# Power_management.net
KiCad netlist of a schematic drawn in Altium Designer
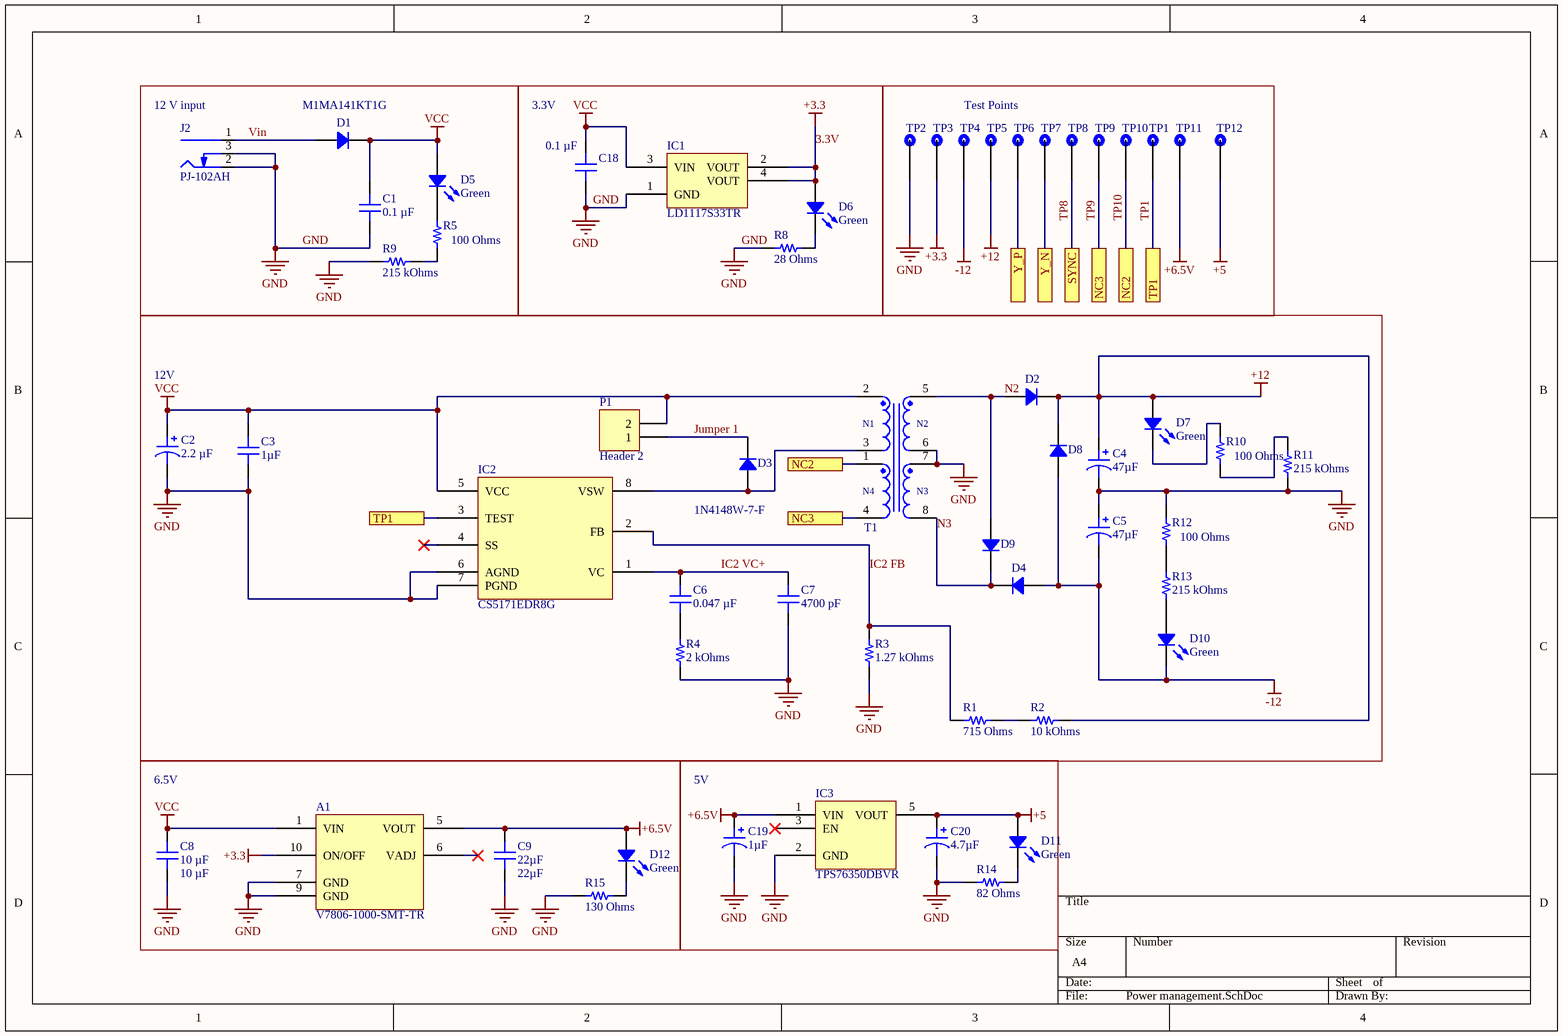
[diagram p0: Power management.SchDoc]

(export (version "E")
  (design (tool "Eeschema 10.0.6"))
  (components
    (comp (ref "A1")
      (value "V7806-1000-SMT-TR")
      (footprint "CUI V78")
      (description "DC DC CONVERTER 6.5V 7W")
      (libsource (lib "Celestial Altium Library - altium_library(1)") (part "CUI V78"))
    )
    (comp (ref "C1")
      (value "0.1 µF")
      (footprint "CAP 0805_2012")
      (description ".100UF 50.0V")
      (fields (field (name "PART NUMBER") "C0805X104K5RAC7210") (field (name "MANUFACTURER") "KEMET"))
      (libsource (lib "Celestial Altium Library - altium_library(1)") (part "Capacitor"))
    )
    (comp (ref "C2")
      (value "2.2 µF")
      (footprint "CAP AL TH D8 L3.5 H12.5")
      (description "CAP ALUM 2.2UF 20% 400V RADIAL")
      (fields (field (name "PART NUMBER") "UVY2G2R2MPD") (field (name "MANUFACTURER") "Nichicon"))
      (libsource (lib "Celestial Altium Library - altium_library(1)") (part "Polarised Capacitor"))
    )
    (comp (ref "C3")
      (value "1µF")
      (footprint "CAP 1206_3216 - 1.0MM")
      (description "CAP CER 1UF 50V X7R 1206")
      (fields (field (name "PART NUMBER") "12065C105K4Z2A") (field (name "MANUFACTURER") "AVX Corporation"))
      (libsource (lib "Celestial Altium Library - altium_library(1)") (part "Capacitor"))
    )
    (comp (ref "C4")
      (value "47µF")
      (footprint "CAP TH ALUM ELEC D6.30mm S2.50mm H12.70mm")
      (description "AL LYTIC, RADIAL, 50VDC, 47UF")
      (fields
        (field (name "PART NUMBER") "EEU-FR1H470")
        (field (name "MANUFACTURER") "Panasonic Electronic Components")
      )
      (libsource (lib "Celestial Altium Library - altium_library(1)") (part "Polarised Capacitor"))
    )
    (comp (ref "C5")
      (value "47µF")
      (footprint "CAP TH ALUM ELEC D6.30mm S2.50mm H12.70mm")
      (description "AL LYTIC, RADIAL, 50VDC, 47UF")
      (fields
        (field (name "PART NUMBER") "EEU-FR1H470")
        (field (name "MANUFACTURER") "Panasonic Electronic Components")
      )
      (libsource (lib "Celestial Altium Library - altium_library(1)") (part "Polarised Capacitor"))
    )
    (comp (ref "C6")
      (value "0.047 µF")
      (footprint "CAP 1206_3216 - 0.8MM")
      (description "CAP CER 1206 47NF 50V X7R 10%")
      (fields (field (name "PART NUMBER") "C1206C473K5RECAUTO") (field (name "MANUFACTURER") "KEMET"))
      (libsource (lib "Celestial Altium Library - altium_library(1)") (part "Capacitor"))
    )
    (comp (ref "C7")
      (value "4700 pF")
      (footprint "CAP 1206_3216 - 0.8MM")
      (description "CAP1206 COG 4700PF 2% 50V")
      (fields
        (field (name "PART NUMBER") "GMC31CG472G50NT")
        (field (name "MANUFACTURER") "Cal-Chip Electronics, Inc.")
      )
      (libsource (lib "Celestial Altium Library - altium_library(1)") (part "Capacitor"))
    )
    (comp (ref "C8")
      (value "10 µF")
      (footprint "CAP 1210_3225 - 1MM")
      (description "CAP CER 10UF 50V X7S 1210")
      (fields (field (name "PART NUMBER") "GCJ32EC71H106KA01L") (field (name "ALTIUM_VALUE") "10 µF"))
      (libsource (lib "Celestial Altium Library - altium_library(1)") (part "Capacitor"))
    )
    (comp (ref "C9")
      (value "22µF")
      (footprint "CAP 1210_3225 - 2.8MM")
      (description "CAP CER 22UF 25V X5R 1210")
      (fields (field (name "PART NUMBER") "12103D226KAT2A") (field (name "ALTIUM_VALUE") "22µF"))
      (libsource (lib "Celestial Altium Library - altium_library(1)") (part "Capacitor"))
    )
    (comp (ref "C18")
      (value "0.1 µF")
      (footprint "CAP 1210_3225 - 1MM")
      (description ".100UF  200V")
      (fields (field (name "PART NUMBER") "C1210J104K2RAC7800") (field (name "MANUFACTURER") "KEMET"))
      (libsource (lib "Celestial Altium Library - altium_library(1)") (part "Capacitor"))
    )
    (comp (ref "C19")
      (value "1µF")
      (footprint "CAP TH ALUM ELEC D4.00mm S1.50mm H6.00mm")
      (description "CAP ALUM 1UF 20% 35V RADIAL")
      (fields (field (name "PART NUMBER") "UMF1V010MDD") (field (name "MANUFACTURER") "Nichicon"))
      (libsource (lib "Celestial Altium Library - altium_library(1)") (part "Polarised Capacitor"))
    )
    (comp (ref "C20")
      (value "4.7µF")
      (footprint "CAP TH ALUM ELEC D4.00mm S1.50mm H6.00mm")
      (description "CAP ALUM 4.7UF 20% 35V RADIAL")
      (fields (field (name "PART NUMBER") "UMF1V4R7MDD") (field (name "MANUFACTURER") "Nichicon"))
      (libsource (lib "Celestial Altium Library - altium_library(1)") (part "Polarised Capacitor"))
    )
    (comp (ref "D1")
      (value "M1MA141KT1G")
      (footprint "DIODES SOT-323-3")
      (description "DIODE GEN PURP 40V 100MA SC70-3")
      (fields (field (name "MANUFACTURER") "ON Semiconductor"))
      (libsource (lib "Celestial Altium Library - altium_library(1)") (part "Diode"))
    )
    (comp (ref "D2")
      (value "MBRS140T3G")
      (footprint "DO214AA SMB")
      (description "DIODE SCHOTTKY 40V 1A SMB")
      (fields (field (name "MANUFACTURER") "ON Semiconductor"))
      (libsource (lib "Celestial Altium Library - altium_library(1)") (part "Diode"))
    )
    (comp (ref "D3")
      (value "1N4148W-7-F")
      (footprint "SOD-123")
      (description "DIODE GEN PURP 100V 300MA SOD123")
      (fields (field (name "MANUFACTURER") "Diodes Incorporated"))
      (libsource (lib "Celestial Altium Library - altium_library(1)") (part "Diode"))
    )
    (comp (ref "D4")
      (value "MBRS140T3G")
      (footprint "DO214AA SMB")
      (description "DIODE SCHOTTKY 40V 1A SMB")
      (fields (field (name "MANUFACTURER") "ON Semiconductor"))
      (libsource (lib "Celestial Altium Library - altium_library(1)") (part "Diode"))
    )
    (comp (ref "D5")
      (value "Green")
      (footprint "LED 1206_3216 GREEN")
      (description "LED GREEN CLEAR 2SMD")
      (fields (field (name "PART NUMBER") "XZVG60W") (field (name "MANUFACTURER") "SunLED"))
      (libsource (lib "Celestial Altium Library - altium_library(1)") (part "LED"))
    )
    (comp (ref "D6")
      (value "Green")
      (footprint "LED 1206_3216 GREEN")
      (description "LED GREEN CLEAR 2SMD")
      (fields (field (name "PART NUMBER") "XZVG60W") (field (name "MANUFACTURER") "SunLED"))
      (libsource (lib "Celestial Altium Library - altium_library(1)") (part "LED"))
    )
    (comp (ref "D7")
      (value "Green")
      (footprint "LED 1206_3216 GREEN")
      (description "LED GREEN CLEAR 2SMD")
      (fields (field (name "PART NUMBER") "XZVG60W") (field (name "MANUFACTURER") "SunLED"))
      (libsource (lib "Celestial Altium Library - altium_library(1)") (part "LED"))
    )
    (comp (ref "D8")
      (value "MBRS140T3G")
      (footprint "DO214AA SMB")
      (description "DIODE SCHOTTKY 40V 1A SMB")
      (fields (field (name "MANUFACTURER") "ON Semiconductor"))
      (libsource (lib "Celestial Altium Library - altium_library(1)") (part "Diode"))
    )
    (comp (ref "D9")
      (value "MBRS140T3G")
      (footprint "DO214AA SMB")
      (description "DIODE SCHOTTKY 40V 1A SMB")
      (fields (field (name "MANUFACTURER") "ON Semiconductor"))
      (libsource (lib "Celestial Altium Library - altium_library(1)") (part "Diode"))
    )
    (comp (ref "D10")
      (value "Green")
      (footprint "LED 1206_3216 GREEN")
      (description "LED GREEN CLEAR 2SMD")
      (fields (field (name "PART NUMBER") "XZVG60W") (field (name "MANUFACTURER") "SunLED"))
      (libsource (lib "Celestial Altium Library - altium_library(1)") (part "LED"))
    )
    (comp (ref "D11")
      (value "Green")
      (footprint "LED 1206_3216 GREEN")
      (description "LED GREEN CLEAR 2SMD")
      (fields (field (name "PART NUMBER") "XZVG60W") (field (name "MANUFACTURER") "SunLED"))
      (libsource (lib "Celestial Altium Library - altium_library(1)") (part "LED"))
    )
    (comp (ref "D12")
      (value "Green")
      (footprint "LED 1206_3216 GREEN")
      (description "LED GREEN CLEAR 2SMD")
      (fields (field (name "PART NUMBER") "XZVG60W") (field (name "MANUFACTURER") "SunLED"))
      (libsource (lib "Celestial Altium Library - altium_library(1)") (part "LED"))
    )
    (comp (ref "IC1")
      (value "LD1117S33TR")
      (footprint "ST SOT-223")
      (description "IC REG LINEAR 3.3V 800MA SOT223")
      (fields (field (name "MANUFACTURER") "STMicroelectronics"))
      (libsource (lib "Celestial Altium Library - altium_library(1)") (part "ST LD1117"))
    )
    (comp (ref "IC2")
      (value "CS5171EDR8G")
      (footprint "ON SEMI SO-8")
      (description "IC REG MULT CONFG ADJ 1.5A 8SOIC")
      (fields (field (name "MANUFACTURER") "ON Semiconductor"))
      (libsource (lib "Celestial Altium Library - altium_library(1)") (part "ON Semi CS5171/3"))
    )
    (comp (ref "IC3")
      (value "TPS76350DBVR")
      (footprint "TI SOT-23-5 DBV")
      (description "IC REG LINEAR 5V 150MA SOT23-5")
      (fields (field (name "MANUFACTURER") "Texas Instruments"))
      (libsource (lib "Celestial Altium Library - altium_library(1)") (part "TI TPS763xx"))
    )
    (comp (ref "J2")
      (value "PJ-102AH")
      (footprint "CUI PJ-102AH")
      (description "CONN PWR JACK 2X5.5MM SOLDER")
      (fields (field (name "MANUFACTURER") "CUI Devices"))
      (libsource (lib "Celestial Altium Library - altium_library(1)") (part "Barrel Connector"))
    )
    (comp (ref "P1")
      (value "Header 2")
      (footprint "HDR1X2")
      (description "Header, 2-Pin")
      (fields (field (name "PUBLISHER") "Altium Limited"))
      (libsource (lib "Miscellaneous Connectors") (part "Header 2"))
    )
    (comp (ref "R1")
      (value "715 Ohms")
      (footprint "RES 1210_3225")
      (description "RES SMD 715 OHM 1% 1/2W 1210")
      (fields (field (name "PART NUMBER") "CRCW1210715RFKEA") (field (name "MANUFACTURER") "Vishay Dale"))
      (libsource (lib "Celestial Altium Library - altium_library(1)") (part "Resistor"))
    )
    (comp (ref "R2")
      (value "10 kOhms")
      (footprint "RES 1210_3225")
      (description "RES SMD 10K OHM 0.5% 1/2W 1210")
      (fields
        (field (name "PART NUMBER") "ERJ-P14D1002U")
        (field (name "MANUFACTURER") "Panasonic Electronic Components")
      )
      (libsource (lib "Celestial Altium Library - altium_library(1)") (part "Resistor"))
    )
    (comp (ref "R3")
      (value "1.27 kOhms")
      (footprint "RES 1210_3225")
      (description "RES SMD 1.27K OHM 1% 1/2W 1210")
      (fields
        (field (name "PART NUMBER") "ERJ-14NF1271U")
        (field (name "MANUFACTURER") "Panasonic Electronic Components")
      )
      (libsource (lib "Celestial Altium Library - altium_library(1)") (part "Resistor"))
    )
    (comp (ref "R4")
      (value "2 kOhms")
      (footprint "RES 1210_3225")
      (description "RES 2K OHM 5% 1/2W 1210")
      (fields (field (name "PART NUMBER") "RC1210JR-072KL") (field (name "MANUFACTURER") "Yageo"))
      (libsource (lib "Celestial Altium Library - altium_library(1)") (part "Resistor"))
    )
    (comp (ref "R5")
      (value "100 Ohms")
      (footprint "RES 2512_6432")
      (description "RES 100 OHM 1% 1W 2512")
      (fields
        (field (name "PART NUMBER") "RK73H3ATTE1000F")
        (field (name "MANUFACTURER") "KOA Speer Electronics, Inc.")
      )
      (libsource (lib "Celestial Altium Library - altium_library(1)") (part "Resistor"))
    )
    (comp (ref "R8")
      (value "28 Ohms")
      (footprint "RES 2512_6432")
      (description "RES 28 OHM 1% 1W 2512")
      (fields
        (field (name "PART NUMBER") "RK73H3ATTE28R0F")
        (field (name "MANUFACTURER") "KOA Speer Electronics, Inc.")
      )
      (libsource (lib "Celestial Altium Library - altium_library(1)") (part "Resistor"))
    )
    (comp (ref "R9")
      (value "215 kOhms")
      (footprint "RES 2512_6432")
      (description "RES SMD 215K OHM 1% 1W 2512")
      (fields (field (name "PART NUMBER") "CRCW2512215KFKEG") (field (name "MANUFACTURER") "Vishay Dale"))
      (libsource (lib "Celestial Altium Library - altium_library(1)") (part "Resistor"))
    )
    (comp (ref "R10")
      (value "100 Ohms")
      (footprint "RES 2512_6432")
      (description "RES 100 OHM 1% 1W 2512")
      (fields
        (field (name "PART NUMBER") "RK73H3ATTE1000F")
        (field (name "MANUFACTURER") "KOA Speer Electronics, Inc.")
      )
      (libsource (lib "Celestial Altium Library - altium_library(1)") (part "Resistor"))
    )
    (comp (ref "R11")
      (value "215 kOhms")
      (footprint "RES 2512_6432")
      (description "RES SMD 215K OHM 1% 1W 2512")
      (fields (field (name "PART NUMBER") "CRCW2512215KFKEG") (field (name "MANUFACTURER") "Vishay Dale"))
      (libsource (lib "Celestial Altium Library - altium_library(1)") (part "Resistor"))
    )
    (comp (ref "R12")
      (value "100 Ohms")
      (footprint "RES 2512_6432")
      (description "RES 100 OHM 1% 1W 2512")
      (fields
        (field (name "PART NUMBER") "RK73H3ATTE1000F")
        (field (name "MANUFACTURER") "KOA Speer Electronics, Inc.")
      )
      (libsource (lib "Celestial Altium Library - altium_library(1)") (part "Resistor"))
    )
    (comp (ref "R13")
      (value "215 kOhms")
      (footprint "RES 2512_6432")
      (description "RES SMD 215K OHM 1% 1W 2512")
      (fields (field (name "PART NUMBER") "CRCW2512215KFKEG") (field (name "MANUFACTURER") "Vishay Dale"))
      (libsource (lib "Celestial Altium Library - altium_library(1)") (part "Resistor"))
    )
    (comp (ref "R14")
      (value "82 Ohms")
      (footprint "RES 2512_6432")
      (description "RES 82 OHM 1% 1W 2512")
      (fields
        (field (name "PART NUMBER") "CRGCQ2512F82R")
        (field (name "MANUFACTURER") "TE Connectivity Passive Product")
      )
      (libsource (lib "Celestial Altium Library - altium_library(1)") (part "Resistor"))
    )
    (comp (ref "R15")
      (value "130 Ohms")
      (footprint "RES 2512_6432")
      (description "RES SMD 130 OHM 1% 1W 2512")
      (fields (field (name "PART NUMBER") "CRCW2512130RFKEG") (field (name "MANUFACTURER") "Vishay Dale"))
      (libsource (lib "Celestial Altium Library - altium_library(1)") (part "Resistor"))
    )
    (comp (ref "T1")
      (value "Ui = 30-57V, Uo1 = 12V/5A, Uo2 = -12V/1.6A")
      (footprint "WE-PoE++_EFD20_THT_L21.08W21.08H10.8")
      (fields
        (field (name "MANUFACTURER PART NUMBER") "750310042")
        (field (name "MANUFACTURER") "Wurth Elektronik")
      )
      (libsource (lib "Altium_WE-PoE++ (rev24a)") (part "750310042"))
    )
    (comp (ref "TP1")
      (value "TP_1")
      (footprint "Test_point_1")
      (libsource (lib "Signal Generator") (part "Test_point_1"))
    )
    (comp (ref "TP2")
      (value "TP_1")
      (footprint "Test_point_1")
      (libsource (lib "Signal Generator") (part "Test_point_1"))
    )
    (comp (ref "TP3")
      (value "TP_1")
      (footprint "Test_point_1")
      (libsource (lib "Signal Generator") (part "Test_point_1"))
    )
    (comp (ref "TP4")
      (value "TP_1")
      (footprint "Test_point_1")
      (libsource (lib "Signal Generator") (part "Test_point_1"))
    )
    (comp (ref "TP5")
      (value "TP_1")
      (footprint "Test_point_1")
      (libsource (lib "Signal Generator") (part "Test_point_1"))
    )
    (comp (ref "TP6")
      (value "TP_1")
      (footprint "Test_point_1")
      (libsource (lib "Signal Generator") (part "Test_point_1"))
    )
    (comp (ref "TP7")
      (value "TP_1")
      (footprint "Test_point_1")
      (libsource (lib "Signal Generator") (part "Test_point_1"))
    )
    (comp (ref "TP8")
      (value "TP_1")
      (footprint "Test_point_1")
      (libsource (lib "Signal Generator") (part "Test_point_1"))
    )
    (comp (ref "TP9")
      (value "TP_1")
      (footprint "Test_point_1")
      (libsource (lib "Signal Generator") (part "Test_point_1"))
    )
    (comp (ref "TP10")
      (value "TP_1")
      (footprint "Test_point_1")
      (libsource (lib "Signal Generator") (part "Test_point_1"))
    )
    (comp (ref "TP11")
      (value "TP_1")
      (footprint "Test_point_1")
      (libsource (lib "Signal Generator") (part "Test_point_1"))
    )
    (comp (ref "TP12")
      (value "TP_1")
      (footprint "Test_point_1")
      (libsource (lib "Signal Generator") (part "Test_point_1"))
    )
  )
  (nets
    (net (code "1") (name "+3.3") (class "Default")
      (node (ref "A1") (pin "10") (pinfunction "ON/OFF_10") (pintype "passive"))
      (node (ref "D6") (pin "1") (pinfunction "1_1") (pintype "passive"))
      (node (ref "IC1") (pin "2") (pinfunction "VOUT_2") (pintype "passive"))
      (node (ref "IC1") (pin "4") (pinfunction "VOUT_4") (pintype "passive"))
      (node (ref "TP3") (pin "TP1") (pinfunction "P1_TP1") (pintype "passive"))
    )
    (net (code "2") (name "+5") (class "Default")
      (node (ref "C20") (pin "1") (pinfunction "1_1") (pintype "passive"))
      (node (ref "D11") (pin "1") (pinfunction "1_1") (pintype "passive"))
      (node (ref "IC3") (pin "5") (pinfunction "VOUT_5") (pintype "passive"))
      (node (ref "TP12") (pin "TP1") (pinfunction "P1_TP1") (pintype "passive"))
    )
    (net (code "3") (name "+6.5V") (class "Default")
      (node (ref "A1") (pin "5") (pinfunction "VOUT_5") (pintype "passive"))
      (node (ref "C19") (pin "1") (pinfunction "1_1") (pintype "passive"))
      (node (ref "C9") (pin "2") (pinfunction "2_2") (pintype "passive"))
      (node (ref "D12") (pin "1") (pinfunction "1_1") (pintype "passive"))
      (node (ref "IC3") (pin "1") (pinfunction "VIN_1") (pintype "passive"))
      (node (ref "TP11") (pin "TP1") (pinfunction "P1_TP1") (pintype "passive"))
    )
    (net (code "4") (name "+12") (class "Default")
      (node (ref "C4") (pin "1") (pinfunction "1_1") (pintype "passive"))
      (node (ref "D2") (pin "2") (pinfunction "2_2") (pintype "passive"))
      (node (ref "D7") (pin "1") (pinfunction "1_1") (pintype "passive"))
      (node (ref "D8") (pin "2") (pinfunction "2_2") (pintype "passive"))
      (node (ref "R2") (pin "2") (pinfunction "2_2") (pintype "passive"))
      (node (ref "TP5") (pin "TP1") (pinfunction "P1_TP1") (pintype "passive"))
    )
    (net (code "5") (name "-12") (class "Default")
      (node (ref "C5") (pin "2") (pinfunction "2_2") (pintype "passive"))
      (node (ref "D10") (pin "2") (pinfunction "2_2") (pintype "passive"))
      (node (ref "D4") (pin "1") (pinfunction "1_1") (pintype "passive"))
      (node (ref "D8") (pin "1") (pinfunction "1_1") (pintype "passive"))
      (node (ref "TP4") (pin "TP1") (pinfunction "P1_TP1") (pintype "passive"))
    )
    (net (code "6") (name "/IC2 FB") (class "Default")
      (node (ref "IC2") (pin "2") (pinfunction "FB_2") (pintype "passive"))
      (node (ref "R1") (pin "1") (pinfunction "1_1") (pintype "passive"))
      (node (ref "R3") (pin "2") (pinfunction "2_2") (pintype "passive"))
    )
    (net (code "7") (name "/IC2 VC+") (class "Default")
      (node (ref "C6") (pin "2") (pinfunction "2_2") (pintype "passive"))
      (node (ref "C7") (pin "2") (pinfunction "2_2") (pintype "passive"))
      (node (ref "IC2") (pin "1") (pinfunction "VC_1") (pintype "passive"))
    )
    (net (code "8") (name "/Jumper 1") (class "Default")
      (node (ref "D3") (pin "2") (pinfunction "2_2") (pintype "passive"))
      (node (ref "P1") (pin "1") (pinfunction "1_1") (pintype "passive"))
    )
    (net (code "9") (name "/N2") (class "Default")
      (node (ref "D2") (pin "1") (pinfunction "1_1") (pintype "passive"))
      (node (ref "D9") (pin "1") (pinfunction "1_1") (pintype "passive"))
      (node (ref "T1") (pin "5") (pinfunction "5_5") (pintype "passive"))
    )
    (net (code "10") (name "/N3") (class "Default")
      (node (ref "D4") (pin "2") (pinfunction "2_2") (pintype "passive"))
      (node (ref "D9") (pin "2") (pinfunction "2_2") (pintype "passive"))
      (node (ref "T1") (pin "8") (pinfunction "8_8") (pintype "passive"))
    )
    (net (code "11") (name "/TP1") (class "Default")
      (node (ref "IC2") (pin "3") (pinfunction "TEST_3") (pintype "passive"))
      (node (ref "TP1") (pin "TP1") (pinfunction "P1_TP1") (pintype "passive"))
    )
    (net (code "12") (name "/TP8") (class "Default")
      (node (ref "TP8") (pin "TP1") (pinfunction "P1_TP1") (pintype "passive"))
    )
    (net (code "13") (name "/TP9") (class "Default")
      (node (ref "T1") (pin "4") (pinfunction "4_4") (pintype "passive"))
      (node (ref "TP9") (pin "TP1") (pinfunction "P1_TP1") (pintype "passive"))
    )
    (net (code "14") (name "/TP10") (class "Default")
      (node (ref "T1") (pin "1") (pinfunction "1_1") (pintype "passive"))
      (node (ref "TP10") (pin "TP1") (pinfunction "P1_TP1") (pintype "passive"))
    )
    (net (code "15") (name "/Vin") (class "Default")
      (node (ref "D1") (pin "1") (pinfunction "1_1") (pintype "passive"))
      (node (ref "J2") (pin "1") (pinfunction "Centre_1") (pintype "passive"))
    )
    (net (code "16") (name "/Y_N") (class "Default")
      (node (ref "TP7") (pin "TP1") (pinfunction "P1_TP1") (pintype "passive"))
    )
    (net (code "17") (name "/Y_P") (class "Default")
      (node (ref "TP6") (pin "TP1") (pinfunction "P1_TP1") (pintype "passive"))
    )
    (net (code "18") (name "GND") (class "Default")
      (node (ref "A1") (pin "7") (pinfunction "GND_7") (pintype "passive"))
      (node (ref "A1") (pin "9") (pinfunction "GND_9") (pintype "passive"))
      (node (ref "C1") (pin "1") (pinfunction "1_1") (pintype "passive"))
      (node (ref "C18") (pin "1") (pinfunction "1_1") (pintype "passive"))
      (node (ref "C19") (pin "2") (pinfunction "2_2") (pintype "passive"))
      (node (ref "C2") (pin "2") (pinfunction "2_2") (pintype "passive"))
      (node (ref "C20") (pin "2") (pinfunction "2_2") (pintype "passive"))
      (node (ref "C3") (pin "1") (pinfunction "1_1") (pintype "passive"))
      (node (ref "C4") (pin "2") (pinfunction "2_2") (pintype "passive"))
      (node (ref "C5") (pin "1") (pinfunction "1_1") (pintype "passive"))
      (node (ref "C7") (pin "1") (pinfunction "1_1") (pintype "passive"))
      (node (ref "C8") (pin "1") (pinfunction "1_1") (pintype "passive"))
      (node (ref "C9") (pin "1") (pinfunction "1_1") (pintype "passive"))
      (node (ref "IC1") (pin "1") (pinfunction "GND_1") (pintype "passive"))
      (node (ref "IC2") (pin "6") (pinfunction "AGND_6") (pintype "passive"))
      (node (ref "IC2") (pin "7") (pinfunction "PGND_7") (pintype "passive"))
      (node (ref "IC3") (pin "2") (pinfunction "GND_2") (pintype "passive"))
      (node (ref "J2") (pin "2") (pinfunction "Outer_2") (pintype "passive"))
      (node (ref "J2") (pin "3") (pinfunction "SW_3") (pintype "passive"))
      (node (ref "R11") (pin "1") (pinfunction "1_1") (pintype "passive"))
      (node (ref "R12") (pin "2") (pinfunction "2_2") (pintype "passive"))
      (node (ref "R14") (pin "1") (pinfunction "1_1") (pintype "passive"))
      (node (ref "R15") (pin "1") (pinfunction "1_1") (pintype "passive"))
      (node (ref "R3") (pin "1") (pinfunction "1_1") (pintype "passive"))
      (node (ref "R4") (pin "1") (pinfunction "1_1") (pintype "passive"))
      (node (ref "R8") (pin "1") (pinfunction "1_1") (pintype "passive"))
      (node (ref "R9") (pin "1") (pinfunction "1_1") (pintype "passive"))
      (node (ref "T1") (pin "6") (pinfunction "6_6") (pintype "passive"))
      (node (ref "T1") (pin "7") (pinfunction "7_7") (pintype "passive"))
      (node (ref "TP2") (pin "TP1") (pinfunction "P1_TP1") (pintype "passive"))
    )
    (net (code "19") (name "Net-(C6-Pad1)") (class "Default")
      (node (ref "C6") (pin "1") (pinfunction "1_1") (pintype "passive"))
      (node (ref "R4") (pin "2") (pinfunction "2_2") (pintype "passive"))
    )
    (net (code "20") (name "Net-(D5-Pad2)") (class "Default")
      (node (ref "D5") (pin "2") (pinfunction "2_2") (pintype "passive"))
      (node (ref "R5") (pin "2") (pinfunction "2_2") (pintype "passive"))
    )
    (net (code "21") (name "Net-(D6-Pad2)") (class "Default")
      (node (ref "D6") (pin "2") (pinfunction "2_2") (pintype "passive"))
      (node (ref "R8") (pin "2") (pinfunction "2_2") (pintype "passive"))
    )
    (net (code "22") (name "Net-(D7-Pad2)") (class "Default")
      (node (ref "D7") (pin "2") (pinfunction "2_2") (pintype "passive"))
      (node (ref "R10") (pin "2") (pinfunction "2_2") (pintype "passive"))
    )
    (net (code "23") (name "Net-(D10-Pad1)") (class "Default")
      (node (ref "D10") (pin "1") (pinfunction "1_1") (pintype "passive"))
      (node (ref "R13") (pin "1") (pinfunction "1_1") (pintype "passive"))
    )
    (net (code "24") (name "Net-(D11-Pad2)") (class "Default")
      (node (ref "D11") (pin "2") (pinfunction "2_2") (pintype "passive"))
      (node (ref "R14") (pin "2") (pinfunction "2_2") (pintype "passive"))
    )
    (net (code "25") (name "Net-(D12-Pad2)") (class "Default")
      (node (ref "D12") (pin "2") (pinfunction "2_2") (pintype "passive"))
      (node (ref "R15") (pin "2") (pinfunction "2_2") (pintype "passive"))
    )
    (net (code "26") (name "Net-(IC2-VSW)") (class "Default")
      (node (ref "D3") (pin "1") (pinfunction "1_1") (pintype "passive"))
      (node (ref "IC2") (pin "8") (pinfunction "VSW_8") (pintype "passive"))
      (node (ref "T1") (pin "3") (pinfunction "3_3") (pintype "passive"))
    )
    (net (code "27") (name "Net-(R1-Pad2)") (class "Default")
      (node (ref "R1") (pin "2") (pinfunction "2_2") (pintype "passive"))
      (node (ref "R2") (pin "1") (pinfunction "1_1") (pintype "passive"))
    )
    (net (code "28") (name "Net-(R5-Pad1)") (class "Default")
      (node (ref "R5") (pin "1") (pinfunction "1_1") (pintype "passive"))
      (node (ref "R9") (pin "2") (pinfunction "2_2") (pintype "passive"))
    )
    (net (code "29") (name "Net-(R10-Pad1)") (class "Default")
      (node (ref "R10") (pin "1") (pinfunction "1_1") (pintype "passive"))
      (node (ref "R11") (pin "2") (pinfunction "2_2") (pintype "passive"))
    )
    (net (code "30") (name "Net-(R12-Pad1)") (class "Default")
      (node (ref "R12") (pin "1") (pinfunction "1_1") (pintype "passive"))
      (node (ref "R13") (pin "2") (pinfunction "2_2") (pintype "passive"))
    )
    (net (code "31") (name "VCC") (class "Default")
      (node (ref "A1") (pin "1") (pinfunction "VIN_1") (pintype "passive"))
      (node (ref "C1") (pin "2") (pinfunction "2_2") (pintype "passive"))
      (node (ref "C18") (pin "2") (pinfunction "2_2") (pintype "passive"))
      (node (ref "C2") (pin "1") (pinfunction "1_1") (pintype "passive"))
      (node (ref "C3") (pin "2") (pinfunction "2_2") (pintype "passive"))
      (node (ref "C8") (pin "2") (pinfunction "2_2") (pintype "passive"))
      (node (ref "D1") (pin "2") (pinfunction "2_2") (pintype "passive"))
      (node (ref "D5") (pin "1") (pinfunction "1_1") (pintype "passive"))
      (node (ref "IC1") (pin "3") (pinfunction "VIN_3") (pintype "passive"))
      (node (ref "IC2") (pin "5") (pinfunction "VCC_5") (pintype "passive"))
      (node (ref "P1") (pin "2") (pinfunction "2_2") (pintype "passive"))
      (node (ref "T1") (pin "2") (pinfunction "2_2") (pintype "passive"))
    )
    (net (code "32") (name "unconnected-(A1-VADJ-Pad6)") (class "Default")
      (node (ref "A1") (pin "6") (pinfunction "VADJ_6") (pintype "passive+no_connect"))
    )
    (net (code "33") (name "unconnected-(IC2-SS-Pad4)") (class "Default")
      (node (ref "IC2") (pin "4") (pinfunction "SS_4") (pintype "passive+no_connect"))
    )
    (net (code "34") (name "unconnected-(IC3-EN-Pad3)") (class "Default")
      (node (ref "IC3") (pin "3") (pinfunction "EN_3") (pintype "passive+no_connect"))
    )
  )
)
